# Sensors_flying_pcb.net
KiCad netlist of a schematic drawn in Altium Designer
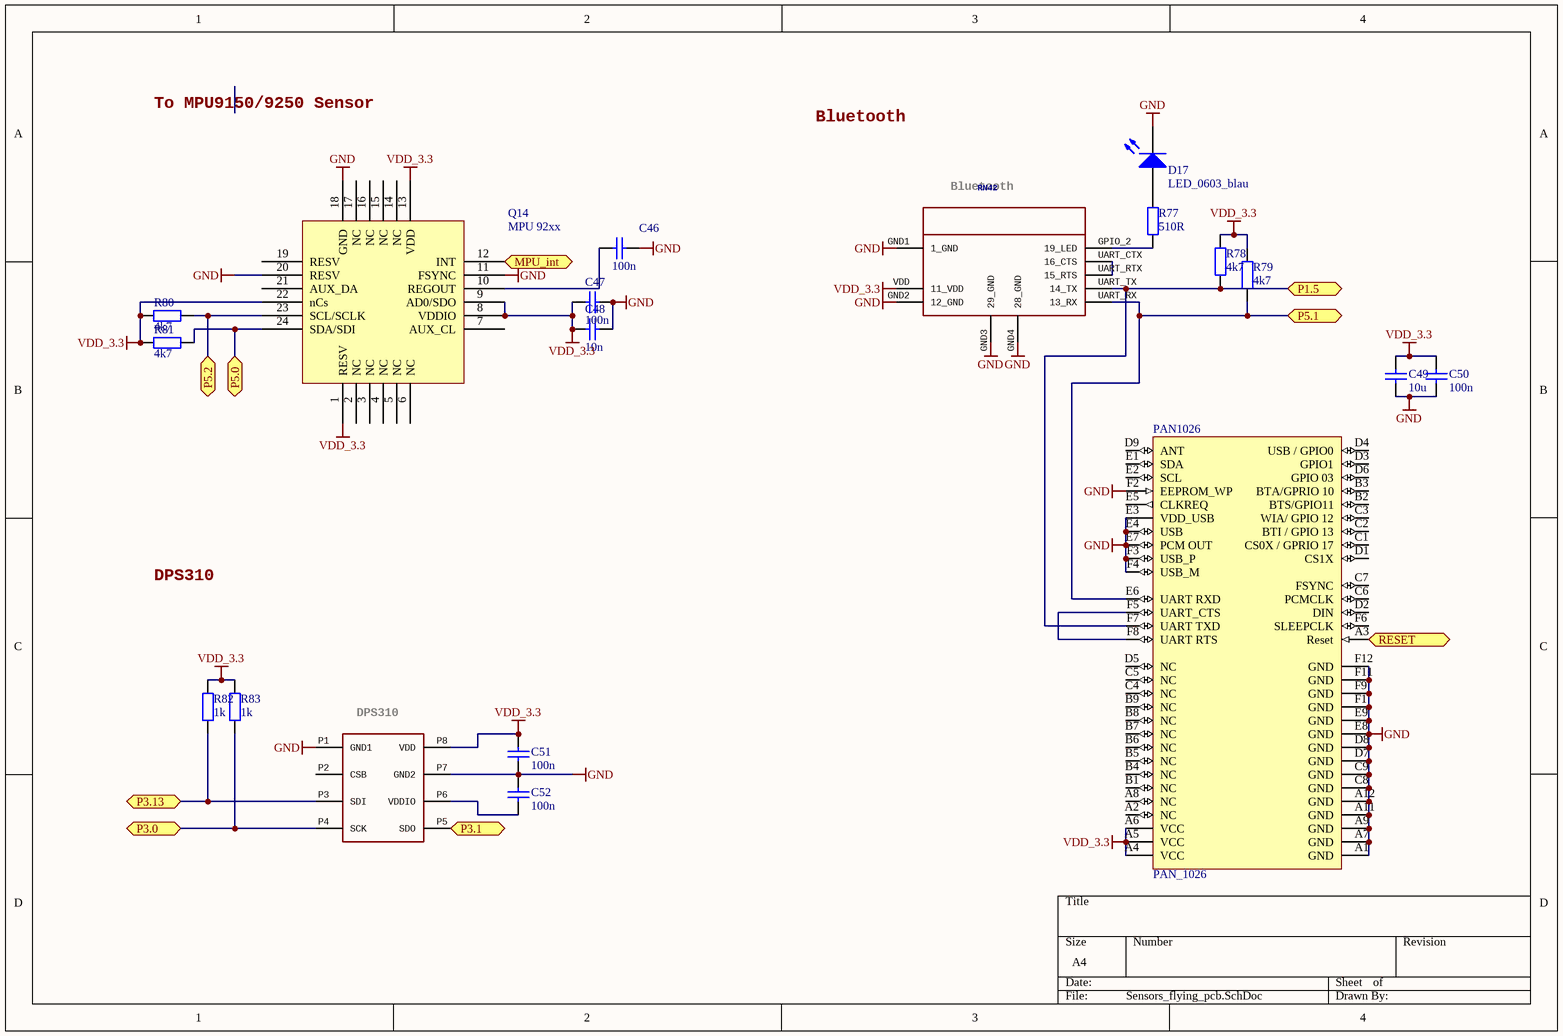
[diagram p0: Sensors_flying_pcb.SchDoc]

(export (version "E")
  (design (tool "Eeschema 10.0.6"))
  (components
    (comp (ref "C46") (value "100n") (footprint "_0603") (libsource (lib "Capacitors$") (part "Cap_129")))
    (comp (ref "C47") (value "100n") (footprint "_0603") (libsource (lib "Capacitors$") (part "Cap_129")))
    (comp (ref "C48") (value "10n") (footprint "_0603") (libsource (lib "Capacitors$") (part "Cap_129")))
    (comp (ref "C49") (value "10u") (footprint "_0603") (libsource (lib "Capacitors$") (part "Cap_129")))
    (comp (ref "C50") (value "100n") (footprint "_0603") (libsource (lib "Capacitors$") (part "Cap_129")))
    (comp (ref "C51") (value "100n") (footprint "_0603") (libsource (lib "Capacitors$") (part "Cap_129")))
    (comp (ref "C52") (value "100n") (footprint "_0603") (libsource (lib "Capacitors$") (part "Cap_129")))
    (comp (ref "D17")
      (value "LED_0603_blau")
      (footprint "LED_0603")
      (libsource (lib "Diodes$") (part "DIODE_60"))
    )
    (comp (ref "DPS310")
      (value "Infineon")
      (footprint "LGA8R125P0X4_500X300X120")
      (libsource (lib "libdrucksensorDPS310") (part "DPS310DRUCKSENSOR"))
    )
    (comp (ref "PAN1026")
      (value "PAN_1026")
      (footprint "LGA49C120P12X6_1560X870X180")
      (libsource (lib "Panasonic_Bluetooth") (part "PAN_1026"))
    )
    (comp (ref "Q14")
      (value "MPU 92xx")
      (footprint "Miscellaneous$:PQFN40P300X300X100_HS-25M")
      (libsource (lib "Miscellaneous$") (part "MPU 92xx"))
    )
    (comp (ref "R77") (value "510R") (footprint "_0603") (libsource (lib "") (part "Res_5_1")))
    (comp (ref "R78") (value "4k7") (footprint "_0603") (libsource (lib "") (part "Res_5_1")))
    (comp (ref "R79") (value "4k7") (footprint "_0603") (libsource (lib "") (part "Res_5_1")))
    (comp (ref "R80") (value "4k7") (footprint "_0603") (libsource (lib "Resistors$") (part "Res_5")))
    (comp (ref "R81") (value "4k7") (footprint "_0603") (libsource (lib "Resistors$") (part "Res_5")))
    (comp (ref "R82") (value "1k") (footprint "_0603") (libsource (lib "") (part "Res_5_2")))
    (comp (ref "R83") (value "1k") (footprint "_0603") (libsource (lib "") (part "Res_5_2")))
    (comp (ref "RN42")
      (value "n.m.")
      (footprint "RN42+SHIELD")
      (fields (field (name ">NAME") "RN42"))
      (libsource (lib "flying_pcb_v1") (part "BLUETOOTHRN42+SHIELD"))
    )
  )
  (nets
    (net (code "1") (name "/MPU_int") (class "Default")
      (node (ref "Q14") (pin "12") (pinfunction "INT_12") (pintype "passive"))
    )
    (net (code "2") (name "/P1.5") (class "Default")
      (node (ref "PAN1026") (pin "F7") (pinfunction "UART_TXD_F7") (pintype "bidirectional"))
      (node (ref "R78") (pin "2") (pinfunction "2_2") (pintype "passive"))
      (node (ref "RN42") (pin "UART_TX") (pinfunction "14_TX_UART_TX") (pintype "passive"))
    )
    (net (code "3") (name "/P3.0") (class "Default")
      (node (ref "DPS310") (pin "P4") (pinfunction "SCK_P4") (pintype "passive"))
      (node (ref "R83") (pin "1") (pinfunction "1_1") (pintype "passive"))
    )
    (net (code "4") (name "/P3.1") (class "Default")
      (node (ref "DPS310") (pin "P5") (pinfunction "SDO_P5") (pintype "passive"))
    )
    (net (code "5") (name "/P3.13") (class "Default")
      (node (ref "DPS310") (pin "P3") (pinfunction "SDI_P3") (pintype "passive"))
      (node (ref "R82") (pin "1") (pinfunction "1_1") (pintype "passive"))
    )
    (net (code "6") (name "/P5.0") (class "Default")
      (node (ref "Q14") (pin "24") (pinfunction "SDA/SDI_24") (pintype "passive"))
      (node (ref "R81") (pin "1") (pinfunction "1_1") (pintype "passive"))
    )
    (net (code "7") (name "/P5.1") (class "Default")
      (node (ref "PAN1026") (pin "E6") (pinfunction "UART_RXD_E6") (pintype "bidirectional"))
      (node (ref "R79") (pin "2") (pinfunction "2_2") (pintype "passive"))
      (node (ref "RN42") (pin "UART_RX") (pinfunction "13_RX_UART_RX") (pintype "passive"))
    )
    (net (code "8") (name "/P5.2") (class "Default")
      (node (ref "Q14") (pin "23") (pinfunction "SCL/SCLK_23") (pintype "passive"))
      (node (ref "R80") (pin "1") (pinfunction "1_1") (pintype "passive"))
    )
    (net (code "9") (name "/RESET") (class "Default")
      (node (ref "PAN1026") (pin "A3") (pinfunction "Reset_A3") (pintype "input"))
    )
    (net (code "10") (name "GND") (class "Default")
      (node (ref "C46") (pin "1") (pinfunction "1_1") (pintype "passive"))
      (node (ref "C47") (pin "1") (pinfunction "1_1") (pintype "passive"))
      (node (ref "C48") (pin "1") (pinfunction "1_1") (pintype "passive"))
      (node (ref "C49") (pin "1") (pinfunction "1_1") (pintype "passive"))
      (node (ref "C50") (pin "1") (pinfunction "1_1") (pintype "passive"))
      (node (ref "C51") (pin "1") (pinfunction "1_1") (pintype "passive"))
      (node (ref "C52") (pin "1") (pinfunction "1_1") (pintype "passive"))
      (node (ref "D17") (pin "2") (pinfunction "2_2") (pintype "passive"))
      (node (ref "DPS310") (pin "P1") (pinfunction "GND1_P1") (pintype "passive"))
      (node (ref "DPS310") (pin "P7") (pinfunction "GND2_P7") (pintype "passive"))
      (node (ref "PAN1026") (pin "A1") (pinfunction "GND_A1") (pintype "power_in"))
      (node (ref "PAN1026") (pin "A11") (pinfunction "GND_A11") (pintype "power_in"))
      (node (ref "PAN1026") (pin "A12") (pinfunction "GND_A12") (pintype "power_in"))
      (node (ref "PAN1026") (pin "A7") (pinfunction "GND_A7") (pintype "power_in"))
      (node (ref "PAN1026") (pin "A9") (pinfunction "GND_A9") (pintype "power_in"))
      (node (ref "PAN1026") (pin "C8") (pinfunction "GND_C8") (pintype "power_in"))
      (node (ref "PAN1026") (pin "C9") (pinfunction "GND_C9") (pintype "power_in"))
      (node (ref "PAN1026") (pin "D7") (pinfunction "GND_D7") (pintype "power_in"))
      (node (ref "PAN1026") (pin "D8") (pinfunction "GND_D8") (pintype "power_in"))
      (node (ref "PAN1026") (pin "E3") (pinfunction "VDD_USB_E3") (pintype "power_in"))
      (node (ref "PAN1026") (pin "E4") (pinfunction "USB_E4") (pintype "bidirectional"))
      (node (ref "PAN1026") (pin "E7") (pinfunction "PCM_OUT_E7") (pintype "bidirectional"))
      (node (ref "PAN1026") (pin "E8") (pinfunction "GND_E8") (pintype "power_in"))
      (node (ref "PAN1026") (pin "E9") (pinfunction "GND_E9") (pintype "power_in"))
      (node (ref "PAN1026") (pin "F1") (pinfunction "GND_F1") (pintype "power_in"))
      (node (ref "PAN1026") (pin "F11") (pinfunction "GND_F11") (pintype "power_in"))
      (node (ref "PAN1026") (pin "F12") (pinfunction "GND_F12") (pintype "power_in"))
      (node (ref "PAN1026") (pin "F2") (pinfunction "EEPROM_WP_F2") (pintype "input"))
      (node (ref "PAN1026") (pin "F3") (pinfunction "USB_P_F3") (pintype "bidirectional"))
      (node (ref "PAN1026") (pin "F4") (pinfunction "USB_M_F4") (pintype "bidirectional"))
      (node (ref "PAN1026") (pin "F9") (pinfunction "GND_F9") (pintype "power_in"))
      (node (ref "Q14") (pin "11") (pinfunction "FSYNC_11") (pintype "passive"))
      (node (ref "Q14") (pin "18") (pinfunction "GND_18") (pintype "passive"))
      (node (ref "Q14") (pin "20") (pinfunction "RESV_20") (pintype "passive"))
      (node (ref "RN42") (pin "GND1") (pinfunction "1_GND_GND1") (pintype "passive"))
      (node (ref "RN42") (pin "GND2") (pinfunction "12_GND_GND2") (pintype "passive"))
      (node (ref "RN42") (pin "GND3") (pinfunction "29_GND_GND3") (pintype "passive"))
      (node (ref "RN42") (pin "GND4") (pinfunction "28_GND_GND4") (pintype "passive"))
    )
    (net (code "11") (name "Net-(D17-Pad1)") (class "Default")
      (node (ref "D17") (pin "1") (pinfunction "1_1") (pintype "passive"))
      (node (ref "R77") (pin "1") (pinfunction "1_1") (pintype "passive"))
    )
    (net (code "12") (name "Net-(DPS310-VDDIO)") (class "Default")
      (node (ref "C52") (pin "2") (pinfunction "2_2") (pintype "passive"))
      (node (ref "DPS310") (pin "P6") (pinfunction "VDDIO_P6") (pintype "passive"))
    )
    (net (code "13") (name "Net-(PAN1026-UART_CTS)") (class "Default")
      (node (ref "PAN1026") (pin "F5") (pinfunction "UART_CTS_F5") (pintype "bidirectional"))
      (node (ref "PAN1026") (pin "F8") (pinfunction "UART_RTS_F8") (pintype "bidirectional"))
    )
    (net (code "14") (name "Net-(Q14-REGOUT)") (class "Default")
      (node (ref "C46") (pin "2") (pinfunction "2_2") (pintype "passive"))
      (node (ref "Q14") (pin "10") (pinfunction "REGOUT_10") (pintype "passive"))
    )
    (net (code "15") (name "Net-(RN42-15_RTS)") (class "Default")
      (node (ref "RN42") (pin "UART_CTX") (pinfunction "16_CTS_UART_CTX") (pintype "passive"))
      (node (ref "RN42") (pin "UART_RTX") (pinfunction "15_RTS_UART_RTX") (pintype "passive"))
    )
    (net (code "16") (name "Net-(RN42-19_LED)") (class "Default")
      (node (ref "R77") (pin "2") (pinfunction "2_2") (pintype "passive"))
      (node (ref "RN42") (pin "GPIO_2") (pinfunction "19_LED_GPIO_2") (pintype "passive"))
    )
    (net (code "17") (name "VDD_3.3") (class "Default")
      (node (ref "C47") (pin "2") (pinfunction "2_2") (pintype "passive"))
      (node (ref "C48") (pin "2") (pinfunction "2_2") (pintype "passive"))
      (node (ref "C49") (pin "2") (pinfunction "2_2") (pintype "passive"))
      (node (ref "C50") (pin "2") (pinfunction "2_2") (pintype "passive"))
      (node (ref "C51") (pin "2") (pinfunction "2_2") (pintype "passive"))
      (node (ref "DPS310") (pin "P8") (pinfunction "VDD_P8") (pintype "passive"))
      (node (ref "PAN1026") (pin "A4") (pinfunction "VCC_A4") (pintype "power_in"))
      (node (ref "PAN1026") (pin "A5") (pinfunction "VCC_A5") (pintype "power_in"))
      (node (ref "PAN1026") (pin "A6") (pinfunction "VCC_A6") (pintype "power_in"))
      (node (ref "Q14") (pin "1") (pinfunction "RESV_1") (pintype "passive"))
      (node (ref "Q14") (pin "13") (pinfunction "VDD_13") (pintype "passive"))
      (node (ref "Q14") (pin "22") (pinfunction "nCs_22") (pintype "passive"))
      (node (ref "Q14") (pin "8") (pinfunction "VDDIO_8") (pintype "passive"))
      (node (ref "Q14") (pin "9") (pinfunction "AD0/SDO_9") (pintype "passive"))
      (node (ref "R78") (pin "1") (pinfunction "1_1") (pintype "passive"))
      (node (ref "R79") (pin "1") (pinfunction "1_1") (pintype "passive"))
      (node (ref "R80") (pin "2") (pinfunction "2_2") (pintype "passive"))
      (node (ref "R81") (pin "2") (pinfunction "2_2") (pintype "passive"))
      (node (ref "R82") (pin "2") (pinfunction "2_2") (pintype "passive"))
      (node (ref "R83") (pin "2") (pinfunction "2_2") (pintype "passive"))
      (node (ref "RN42") (pin "VDD") (pinfunction "11_VDD_VDD") (pintype "passive"))
    )
    (net (code "18") (name "unconnected-(DPS310-CSB-PadP2)") (class "Default")
      (node (ref "DPS310") (pin "P2") (pinfunction "CSB_P2") (pintype "passive"))
    )
    (net (code "19") (name "unconnected-(PAN1026-ANT-PadD9)") (class "Default")
      (node (ref "PAN1026") (pin "D9") (pinfunction "ANT_D9") (pintype "bidirectional"))
    )
    (net (code "20") (name "unconnected-(PAN1026-BTA{slash}GPRIO_10-PadB3)") (class "Default")
      (node (ref "PAN1026") (pin "B3") (pinfunction "BTA/GPRIO_10_B3") (pintype "bidirectional"))
    )
    (net (code "21") (name "unconnected-(PAN1026-BTI_{slash}_GPIO_13-PadC2)") (class "Default")
      (node (ref "PAN1026") (pin "C2") (pinfunction "BTI_/_GPIO_13_C2") (pintype "bidirectional"))
    )
    (net (code "22") (name "unconnected-(PAN1026-BTS{slash}GPIO11-PadB2)") (class "Default")
      (node (ref "PAN1026") (pin "B2") (pinfunction "BTS/GPIO11_B2") (pintype "bidirectional"))
    )
    (net (code "23") (name "unconnected-(PAN1026-CLKREQ-PadE5)") (class "Default")
      (node (ref "PAN1026") (pin "E5") (pinfunction "CLKREQ_E5") (pintype "output"))
    )
    (net (code "24") (name "unconnected-(PAN1026-CS0X_{slash}_GPRIO_17-PadC1)") (class "Default")
      (node (ref "PAN1026") (pin "C1") (pinfunction "CS0X_/_GPRIO_17_C1") (pintype "bidirectional"))
    )
    (net (code "25") (name "unconnected-(PAN1026-CS1X-PadD1)") (class "Default")
      (node (ref "PAN1026") (pin "D1") (pinfunction "CS1X_D1") (pintype "bidirectional"))
    )
    (net (code "26") (name "unconnected-(PAN1026-DIN-PadD2)") (class "Default")
      (node (ref "PAN1026") (pin "D2") (pinfunction "DIN_D2") (pintype "bidirectional"))
    )
    (net (code "27") (name "unconnected-(PAN1026-FSYNC-PadC7)") (class "Default")
      (node (ref "PAN1026") (pin "C7") (pinfunction "FSYNC_C7") (pintype "bidirectional"))
    )
    (net (code "28") (name "unconnected-(PAN1026-GPIO1-PadD3)") (class "Default")
      (node (ref "PAN1026") (pin "D3") (pinfunction "GPIO1_D3") (pintype "bidirectional"))
    )
    (net (code "29") (name "unconnected-(PAN1026-GPIO_03-PadD6)") (class "Default")
      (node (ref "PAN1026") (pin "D6") (pinfunction "GPIO_03_D6") (pintype "bidirectional"))
    )
    (net (code "30") (name "unconnected-(PAN1026-NC-PadA2)") (class "Default")
      (node (ref "PAN1026") (pin "A2") (pinfunction "NC_A2") (pintype "bidirectional"))
    )
    (net (code "31") (name "unconnected-(PAN1026-NC-PadA8)") (class "Default")
      (node (ref "PAN1026") (pin "A8") (pinfunction "NC_A8") (pintype "bidirectional"))
    )
    (net (code "32") (name "unconnected-(PAN1026-NC-PadB1)") (class "Default")
      (node (ref "PAN1026") (pin "B1") (pinfunction "NC_B1") (pintype "bidirectional"))
    )
    (net (code "33") (name "unconnected-(PAN1026-NC-PadB4)") (class "Default")
      (node (ref "PAN1026") (pin "B4") (pinfunction "NC_B4") (pintype "bidirectional"))
    )
    (net (code "34") (name "unconnected-(PAN1026-NC-PadB5)") (class "Default")
      (node (ref "PAN1026") (pin "B5") (pinfunction "NC_B5") (pintype "bidirectional"))
    )
    (net (code "35") (name "unconnected-(PAN1026-NC-PadB6)") (class "Default")
      (node (ref "PAN1026") (pin "B6") (pinfunction "NC_B6") (pintype "bidirectional"))
    )
    (net (code "36") (name "unconnected-(PAN1026-NC-PadB7)") (class "Default")
      (node (ref "PAN1026") (pin "B7") (pinfunction "NC_B7") (pintype "bidirectional"))
    )
    (net (code "37") (name "unconnected-(PAN1026-NC-PadB8)") (class "Default")
      (node (ref "PAN1026") (pin "B8") (pinfunction "NC_B8") (pintype "bidirectional"))
    )
    (net (code "38") (name "unconnected-(PAN1026-NC-PadB9)") (class "Default")
      (node (ref "PAN1026") (pin "B9") (pinfunction "NC_B9") (pintype "bidirectional"))
    )
    (net (code "39") (name "unconnected-(PAN1026-NC-PadC4)") (class "Default")
      (node (ref "PAN1026") (pin "C4") (pinfunction "NC_C4") (pintype "bidirectional"))
    )
    (net (code "40") (name "unconnected-(PAN1026-NC-PadC5)") (class "Default")
      (node (ref "PAN1026") (pin "C5") (pinfunction "NC_C5") (pintype "bidirectional"))
    )
    (net (code "41") (name "unconnected-(PAN1026-NC-PadD5)") (class "Default")
      (node (ref "PAN1026") (pin "D5") (pinfunction "NC_D5") (pintype "bidirectional"))
    )
    (net (code "42") (name "unconnected-(PAN1026-PCMCLK-PadC6)") (class "Default")
      (node (ref "PAN1026") (pin "C6") (pinfunction "PCMCLK_C6") (pintype "bidirectional"))
    )
    (net (code "43") (name "unconnected-(PAN1026-SCL-PadE2)") (class "Default")
      (node (ref "PAN1026") (pin "E2") (pinfunction "SCL_E2") (pintype "bidirectional"))
    )
    (net (code "44") (name "unconnected-(PAN1026-SDA-PadE1)") (class "Default")
      (node (ref "PAN1026") (pin "E1") (pinfunction "SDA_E1") (pintype "bidirectional"))
    )
    (net (code "45") (name "unconnected-(PAN1026-SLEEPCLK-PadF6)") (class "Default")
      (node (ref "PAN1026") (pin "F6") (pinfunction "SLEEPCLK_F6") (pintype "bidirectional"))
    )
    (net (code "46") (name "unconnected-(PAN1026-USB_{slash}_GPIO0-PadD4)") (class "Default")
      (node (ref "PAN1026") (pin "D4") (pinfunction "USB_/_GPIO0_D4") (pintype "bidirectional"))
    )
    (net (code "47") (name "unconnected-(PAN1026-WIA{slash}_GPIO_12-PadC3)") (class "Default")
      (node (ref "PAN1026") (pin "C3") (pinfunction "WIA/_GPIO_12_C3") (pintype "bidirectional"))
    )
    (net (code "48") (name "unconnected-(Q14-AUX_CL-Pad7)") (class "Default")
      (node (ref "Q14") (pin "7") (pinfunction "AUX_CL_7") (pintype "passive"))
    )
    (net (code "49") (name "unconnected-(Q14-AUX_DA-Pad21)") (class "Default")
      (node (ref "Q14") (pin "21") (pinfunction "AUX_DA_21") (pintype "passive"))
    )
    (net (code "50") (name "unconnected-(Q14-NC-Pad2)") (class "Default")
      (node (ref "Q14") (pin "2") (pinfunction "NC_2") (pintype "passive"))
    )
    (net (code "51") (name "unconnected-(Q14-NC-Pad3)") (class "Default")
      (node (ref "Q14") (pin "3") (pinfunction "NC_3") (pintype "passive"))
    )
    (net (code "52") (name "unconnected-(Q14-NC-Pad4)") (class "Default")
      (node (ref "Q14") (pin "4") (pinfunction "NC_4") (pintype "passive"))
    )
    (net (code "53") (name "unconnected-(Q14-NC-Pad5)") (class "Default")
      (node (ref "Q14") (pin "5") (pinfunction "NC_5") (pintype "passive"))
    )
    (net (code "54") (name "unconnected-(Q14-NC-Pad6)") (class "Default")
      (node (ref "Q14") (pin "6") (pinfunction "NC_6") (pintype "passive"))
    )
    (net (code "55") (name "unconnected-(Q14-NC-Pad14)") (class "Default")
      (node (ref "Q14") (pin "14") (pinfunction "NC_14") (pintype "passive"))
    )
    (net (code "56") (name "unconnected-(Q14-NC-Pad15)") (class "Default")
      (node (ref "Q14") (pin "15") (pinfunction "NC_15") (pintype "passive"))
    )
    (net (code "57") (name "unconnected-(Q14-NC-Pad16)") (class "Default")
      (node (ref "Q14") (pin "16") (pinfunction "NC_16") (pintype "passive"))
    )
    (net (code "58") (name "unconnected-(Q14-NC-Pad17)") (class "Default")
      (node (ref "Q14") (pin "17") (pinfunction "NC_17") (pintype "passive"))
    )
    (net (code "59") (name "unconnected-(Q14-RESV-Pad19)") (class "Default")
      (node (ref "Q14") (pin "19") (pinfunction "RESV_19") (pintype "passive"))
    )
  )
)
